# OpenCTD-V04.net
KiCad netlist of a schematic drawn in EAGLE
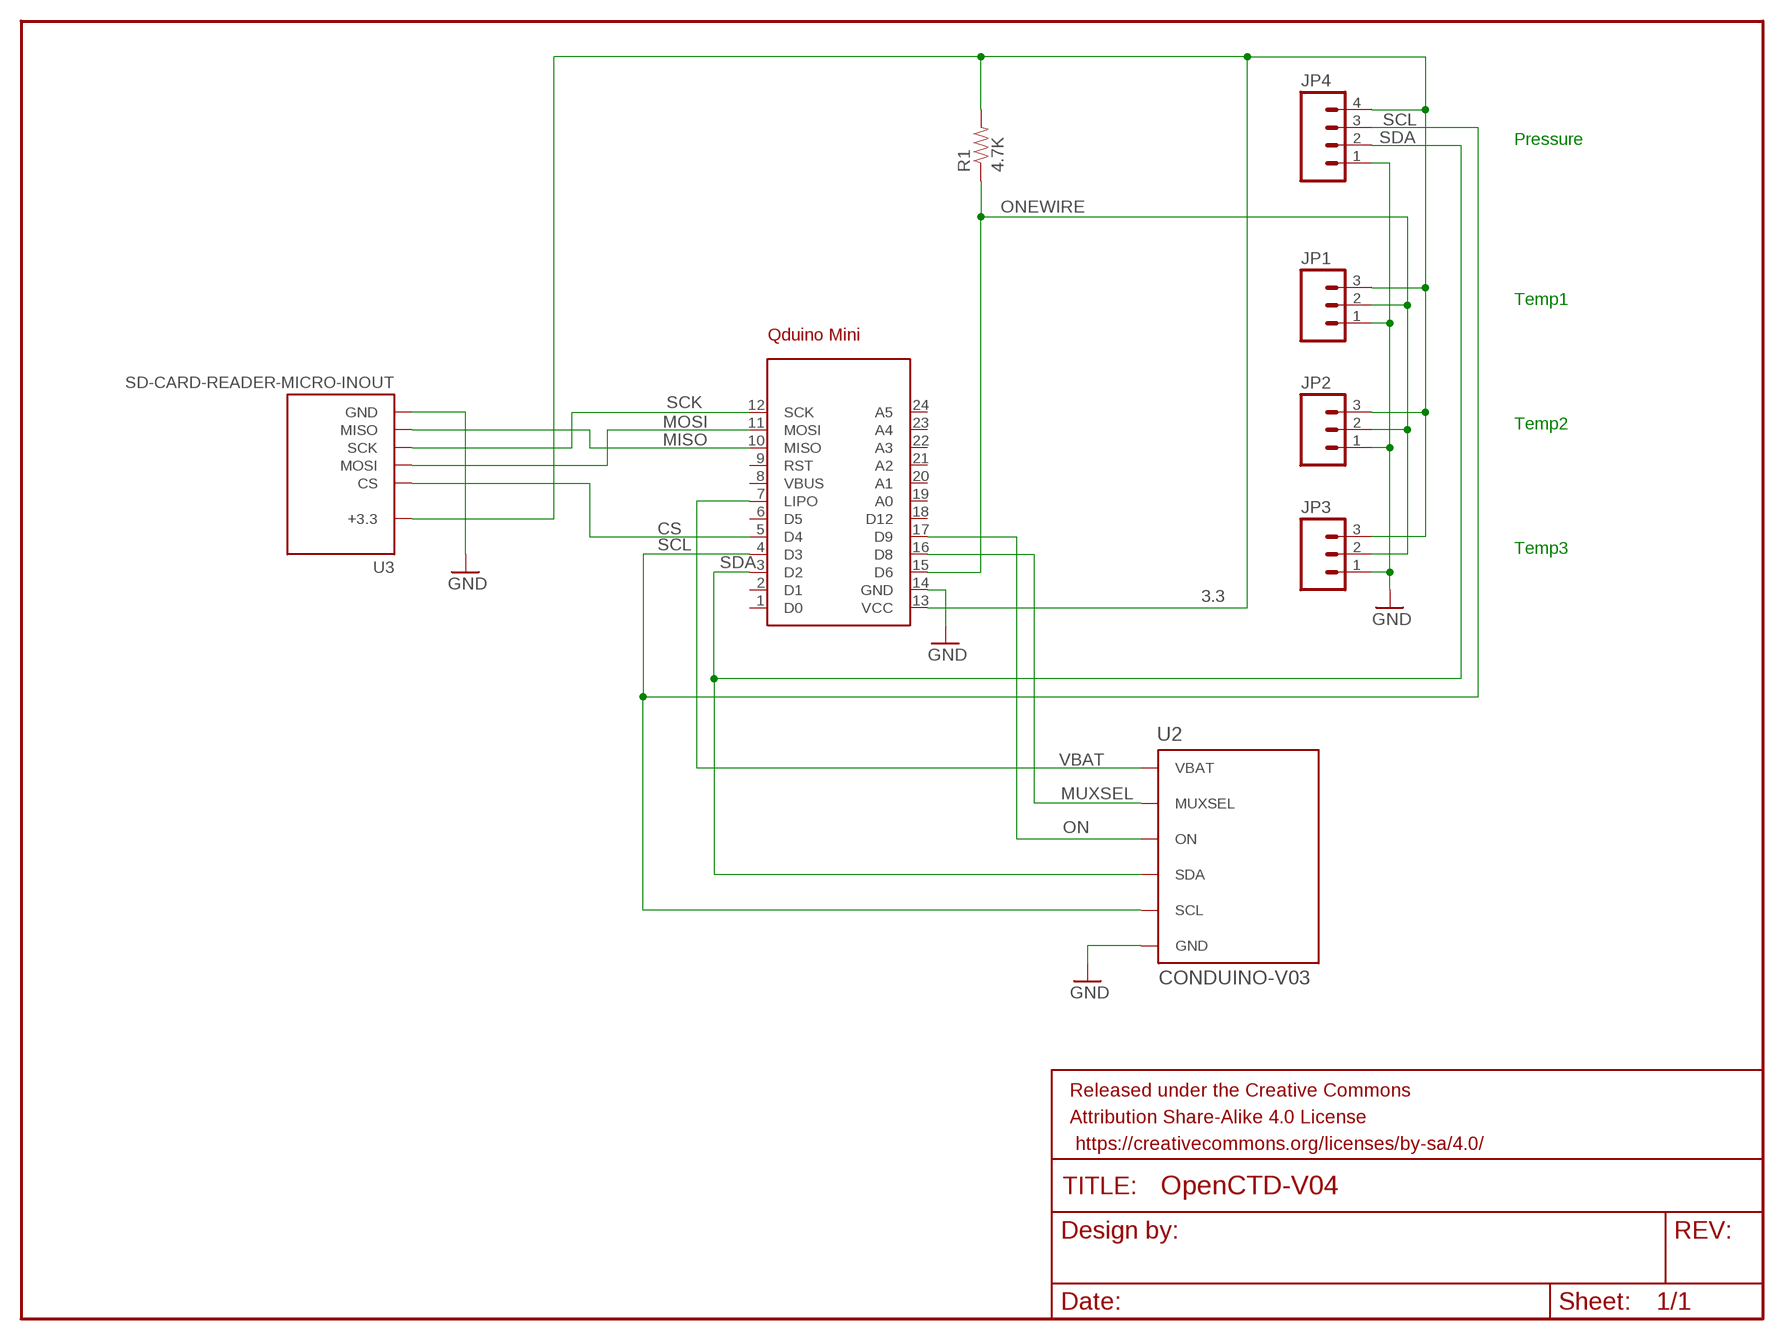
[diagram p0: schematic, sheet 1]

(export (version "E")
  (design (tool "Eeschema 10.0.6"))
  (components
    (comp (ref "FRAME1")
      (value "FRAME-LETTER")
      (footprint "eagle-import:CREATIVE_COMMONS")
      (libsource (lib "eagle-import") (part "FRAME-LETTER"))
    )
    (comp (ref "JP1")
      (value "M031X03_NO_SILK")
      (footprint "eagle-import:1X03_NO_SILK")
      (libsource (lib "eagle-import") (part "M031X03_NO_SILK"))
    )
    (comp (ref "JP2")
      (value "M031X03_NO_SILK")
      (footprint "eagle-import:1X03_NO_SILK")
      (libsource (lib "eagle-import") (part "M031X03_NO_SILK"))
    )
    (comp (ref "JP3")
      (value "M031X03_NO_SILK")
      (footprint "eagle-import:1X03_NO_SILK")
      (libsource (lib "eagle-import") (part "M031X03_NO_SILK"))
    )
    (comp (ref "JP4")
      (value "M041X04_NO_SILK")
      (footprint "eagle-import:1X04_NO_SILK")
      (libsource (lib "eagle-import") (part "M041X04_NO_SILK"))
    )
    (comp (ref "R1")
      (value "4.7K")
      (footprint "eagle-import:AXIAL-0.4")
      (libsource (lib "eagle-import") (part "RESISTORPTH-1/4W"))
    )
    (comp (ref "U1")
      (value "QDUINO_MINI")
      (footprint "eagle-import:QDUINO_MINI")
      (libsource (lib "eagle-import") (part "QDUINO_MINI"))
    )
    (comp (ref "U2")
      (value "CONDUINO-V03")
      (footprint "eagle-import:CONDUINO_V03")
      (libsource (lib "eagle-import") (part "CONDUINO-V03"))
    )
    (comp (ref "U3")
      (value "SD-CARD-READER-MICRO-INOUT")
      (footprint "eagle-import:SD-CARD-READER-105162")
      (libsource (lib "eagle-import") (part "SD-CARD-READER-MICRO-INOUT"))
    )
  )
  (nets
    (net (code "1") (name "/3.3") (class "Default")
      (node (ref "JP1") (pin "3") (pinfunction "3_3") (pintype "passive"))
      (node (ref "JP2") (pin "3") (pinfunction "3_3") (pintype "passive"))
      (node (ref "JP3") (pin "3") (pinfunction "3_3") (pintype "passive"))
      (node (ref "JP4") (pin "4") (pinfunction "4_4") (pintype "passive"))
      (node (ref "R1") (pin "P$2") (pinfunction "2_P$2") (pintype "passive"))
      (node (ref "U1") (pin "13") (pinfunction "VCC_13") (pintype "bidirectional"))
      (node (ref "U3") (pin "P$4") (pinfunction "+3.3_P$4") (pintype "bidirectional"))
    )
    (net (code "2") (name "/CS") (class "Default")
      (node (ref "U1") (pin "5") (pinfunction "D4_5") (pintype "bidirectional"))
      (node (ref "U3") (pin "P$2") (pinfunction "CS_P$2") (pintype "bidirectional"))
    )
    (net (code "3") (name "/MISO") (class "Default")
      (node (ref "U1") (pin "10") (pinfunction "MISO_10") (pintype "bidirectional"))
      (node (ref "U3") (pin "P$7") (pinfunction "MISO_P$7") (pintype "bidirectional"))
    )
    (net (code "4") (name "/MOSI") (class "Default")
      (node (ref "U1") (pin "11") (pinfunction "MOSI_11") (pintype "bidirectional"))
      (node (ref "U3") (pin "P$3") (pinfunction "MOSI_P$3") (pintype "bidirectional"))
    )
    (net (code "5") (name "/MUXSEL") (class "Default")
      (node (ref "U1") (pin "16") (pinfunction "D8_16") (pintype "bidirectional"))
      (node (ref "U2") (pin "4") (pinfunction "MUXSEL_4") (pintype "bidirectional"))
    )
    (net (code "6") (name "/ON") (class "Default")
      (node (ref "U1") (pin "17") (pinfunction "D9_17") (pintype "bidirectional"))
      (node (ref "U2") (pin "3") (pinfunction "ON_3") (pintype "bidirectional"))
    )
    (net (code "7") (name "/ONEWIRE") (class "Default")
      (node (ref "JP1") (pin "2") (pinfunction "2_2") (pintype "passive"))
      (node (ref "JP2") (pin "2") (pinfunction "2_2") (pintype "passive"))
      (node (ref "JP3") (pin "2") (pinfunction "2_2") (pintype "passive"))
      (node (ref "R1") (pin "P$1") (pinfunction "1_P$1") (pintype "passive"))
      (node (ref "U1") (pin "15") (pinfunction "D6_15") (pintype "bidirectional"))
    )
    (net (code "8") (name "/SCK") (class "Default")
      (node (ref "U1") (pin "12") (pinfunction "SCK_12") (pintype "bidirectional"))
      (node (ref "U3") (pin "P$5") (pinfunction "SCK_P$5") (pintype "bidirectional"))
    )
    (net (code "9") (name "/SCL") (class "Default")
      (node (ref "JP4") (pin "3") (pinfunction "3_3") (pintype "passive"))
      (node (ref "U1") (pin "4") (pinfunction "D3_4") (pintype "bidirectional"))
      (node (ref "U2") (pin "1") (pinfunction "SCL_1") (pintype "bidirectional"))
    )
    (net (code "10") (name "/SDA") (class "Default")
      (node (ref "JP4") (pin "2") (pinfunction "2_2") (pintype "passive"))
      (node (ref "U1") (pin "3") (pinfunction "D2_3") (pintype "bidirectional"))
      (node (ref "U2") (pin "2") (pinfunction "SDA_2") (pintype "bidirectional"))
    )
    (net (code "11") (name "/VBAT") (class "Default")
      (node (ref "U1") (pin "7") (pinfunction "LIPO_7") (pintype "bidirectional"))
      (node (ref "U2") (pin "6") (pinfunction "VBAT_6") (pintype "bidirectional"))
    )
    (net (code "12") (name "GND") (class "Default")
      (node (ref "JP1") (pin "1") (pinfunction "1_1") (pintype "passive"))
      (node (ref "JP2") (pin "1") (pinfunction "1_1") (pintype "passive"))
      (node (ref "JP3") (pin "1") (pinfunction "1_1") (pintype "passive"))
      (node (ref "JP4") (pin "1") (pinfunction "1_1") (pintype "passive"))
      (node (ref "U1") (pin "14") (pinfunction "GND_14") (pintype "bidirectional"))
      (node (ref "U2") (pin "5") (pinfunction "GND_5") (pintype "bidirectional"))
      (node (ref "U3") (pin "G1") (pinfunction "GND_G1") (pintype "bidirectional"))
      (node (ref "U3") (pin "G2") (pinfunction "GND_G2") (pintype "bidirectional"))
      (node (ref "U3") (pin "G3") (pinfunction "GND_G3") (pintype "bidirectional"))
      (node (ref "U3") (pin "G4") (pinfunction "GND_G4") (pintype "bidirectional"))
      (node (ref "U3") (pin "P$6") (pinfunction "GND_P$6") (pintype "bidirectional"))
    )
    (net (code "13") (name "unconnected-(U1-A0-Pad19)") (class "Default")
      (node (ref "U1") (pin "19") (pinfunction "A0_19") (pintype "bidirectional"))
    )
    (net (code "14") (name "unconnected-(U1-A1-Pad20)") (class "Default")
      (node (ref "U1") (pin "20") (pinfunction "A1_20") (pintype "bidirectional"))
    )
    (net (code "15") (name "unconnected-(U1-A2-Pad21)") (class "Default")
      (node (ref "U1") (pin "21") (pinfunction "A2_21") (pintype "bidirectional"))
    )
    (net (code "16") (name "unconnected-(U1-A3-Pad22)") (class "Default")
      (node (ref "U1") (pin "22") (pinfunction "A3_22") (pintype "bidirectional"))
    )
    (net (code "17") (name "unconnected-(U1-A4-Pad23)") (class "Default")
      (node (ref "U1") (pin "23") (pinfunction "A4_23") (pintype "bidirectional"))
    )
    (net (code "18") (name "unconnected-(U1-A5-Pad24)") (class "Default")
      (node (ref "U1") (pin "24") (pinfunction "A5_24") (pintype "bidirectional"))
    )
    (net (code "19") (name "unconnected-(U1-D0-Pad1)") (class "Default")
      (node (ref "U1") (pin "1") (pinfunction "D0_1") (pintype "bidirectional"))
    )
    (net (code "20") (name "unconnected-(U1-D1-Pad2)") (class "Default")
      (node (ref "U1") (pin "2") (pinfunction "D1_2") (pintype "bidirectional"))
    )
    (net (code "21") (name "unconnected-(U1-D5-Pad6)") (class "Default")
      (node (ref "U1") (pin "6") (pinfunction "D5_6") (pintype "bidirectional"))
    )
    (net (code "22") (name "unconnected-(U1-D12-Pad18)") (class "Default")
      (node (ref "U1") (pin "18") (pinfunction "D12_18") (pintype "bidirectional"))
    )
    (net (code "23") (name "unconnected-(U1-RST-Pad9)") (class "Default")
      (node (ref "U1") (pin "9") (pinfunction "RST_9") (pintype "bidirectional"))
    )
    (net (code "24") (name "unconnected-(U1-VBUS-Pad8)") (class "Default")
      (node (ref "U1") (pin "8") (pinfunction "VBUS_8") (pintype "bidirectional"))
    )
  )
)
